# GECBalloonMCUFlightBoard_REV2_0_5-6-19.net
KiCad netlist of a schematic drawn in EAGLE
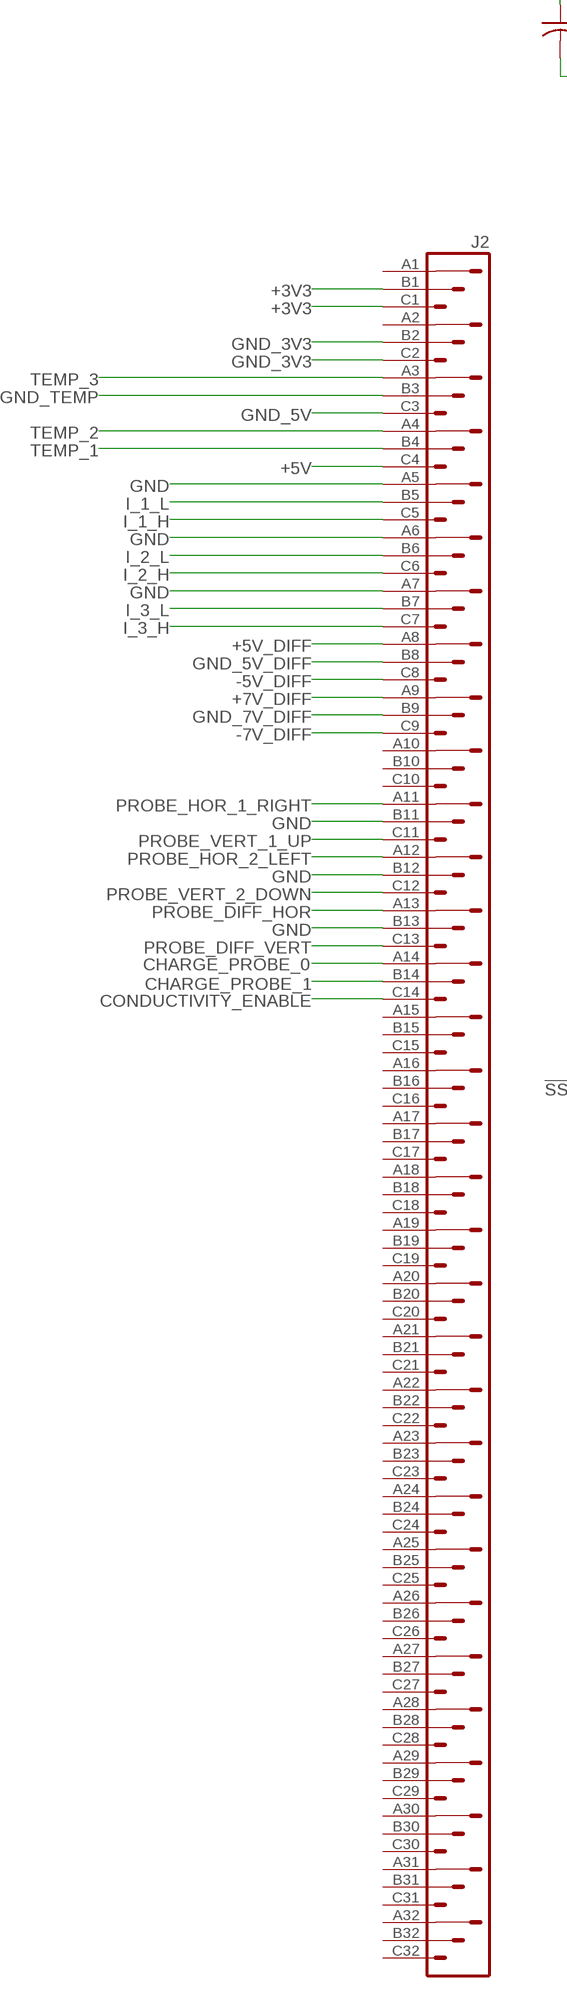
[diagram p0: schematic, sheet 1, part 1 of 2]
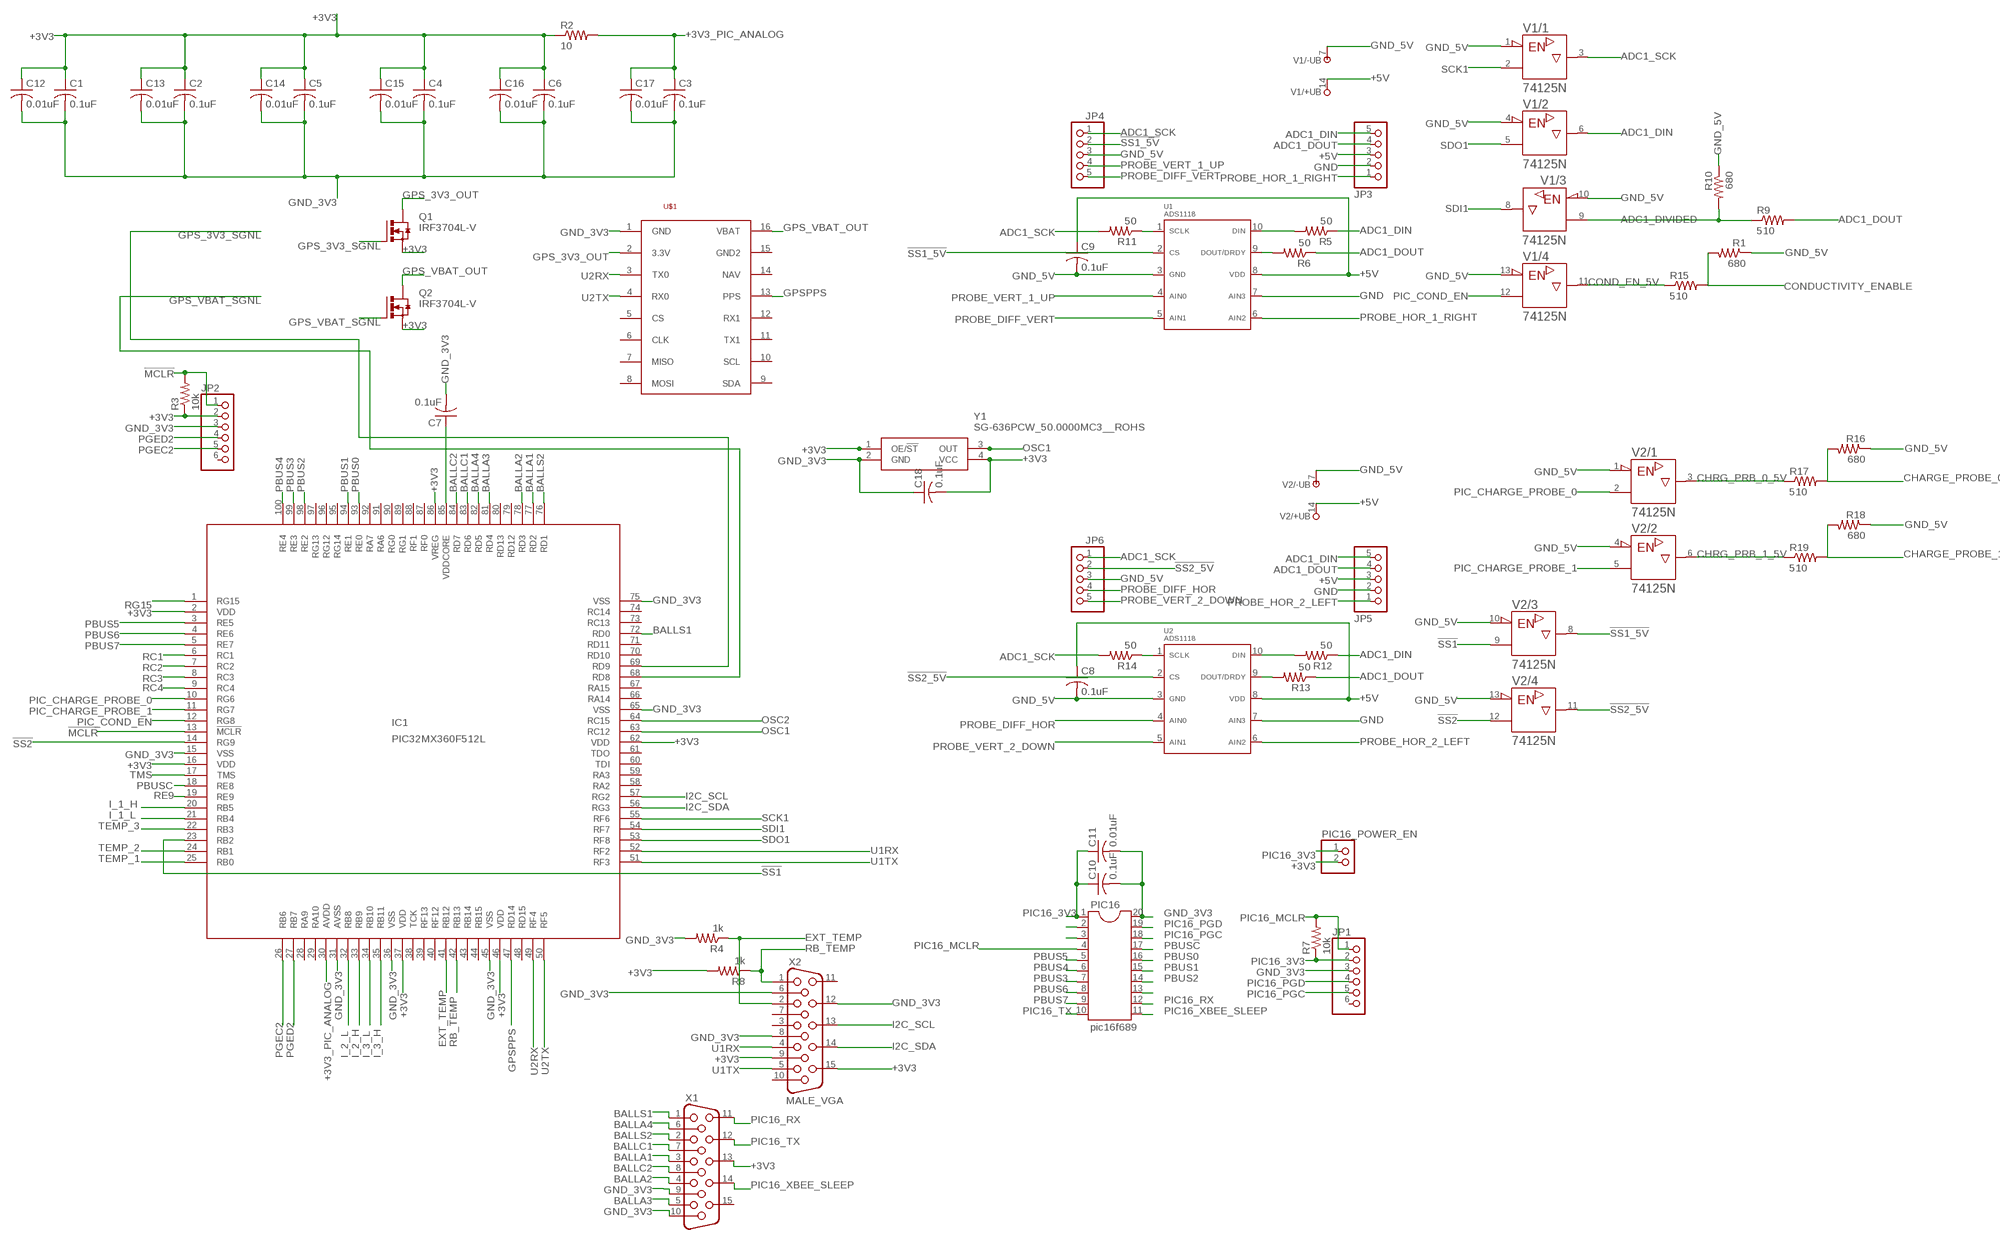
[diagram p1: schematic, sheet 1, part 2 of 2]

(export (version "E")
  (design (tool "Eeschema 10.0.6"))
  (components
    (comp (ref "C1")
      (value "0.1uF")
      (footprint "eagle-import:C1206")
      (libsource (lib "eagle-import") (part "C-USC1206"))
    )
    (comp (ref "C2")
      (value "0.1uF")
      (footprint "eagle-import:C1206")
      (libsource (lib "eagle-import") (part "C-USC1206"))
    )
    (comp (ref "C3")
      (value "0.1uF")
      (footprint "eagle-import:C1206")
      (libsource (lib "eagle-import") (part "C-USC1206"))
    )
    (comp (ref "C4")
      (value "0.1uF")
      (footprint "eagle-import:C1206")
      (libsource (lib "eagle-import") (part "C-USC1206"))
    )
    (comp (ref "C5")
      (value "0.1uF")
      (footprint "eagle-import:C1206")
      (libsource (lib "eagle-import") (part "C-USC1206"))
    )
    (comp (ref "C6")
      (value "0.1uF")
      (footprint "eagle-import:C1206")
      (libsource (lib "eagle-import") (part "C-USC1206"))
    )
    (comp (ref "C7")
      (value "0.1uF")
      (footprint "eagle-import:C1206")
      (libsource (lib "eagle-import") (part "C-USC1206"))
    )
    (comp (ref "C8")
      (value "0.1uF")
      (footprint "eagle-import:C1206")
      (libsource (lib "eagle-import") (part "C-USC1206"))
    )
    (comp (ref "C9")
      (value "0.1uF")
      (footprint "eagle-import:C1206")
      (libsource (lib "eagle-import") (part "C-USC1206"))
    )
    (comp (ref "C10")
      (value "0.1uF")
      (footprint "eagle-import:C1206")
      (libsource (lib "eagle-import") (part "C-USC1206"))
    )
    (comp (ref "C11")
      (value "0.01uF")
      (footprint "eagle-import:C1206")
      (libsource (lib "eagle-import") (part "C-USC1206"))
    )
    (comp (ref "C12")
      (value "0.01uF")
      (footprint "eagle-import:C1206")
      (libsource (lib "eagle-import") (part "C-USC1206"))
    )
    (comp (ref "C13")
      (value "0.01uF")
      (footprint "eagle-import:C1206")
      (libsource (lib "eagle-import") (part "C-USC1206"))
    )
    (comp (ref "C14")
      (value "0.01uF")
      (footprint "eagle-import:C1206")
      (libsource (lib "eagle-import") (part "C-USC1206"))
    )
    (comp (ref "C15")
      (value "0.01uF")
      (footprint "eagle-import:C1206")
      (libsource (lib "eagle-import") (part "C-USC1206"))
    )
    (comp (ref "C16")
      (value "0.01uF")
      (footprint "eagle-import:C1206")
      (libsource (lib "eagle-import") (part "C-USC1206"))
    )
    (comp (ref "C17")
      (value "0.01uF")
      (footprint "eagle-import:C1206")
      (libsource (lib "eagle-import") (part "C-USC1206"))
    )
    (comp (ref "C18")
      (value "0.1uF")
      (footprint "eagle-import:C1206")
      (libsource (lib "eagle-import") (part "C-USC1206"))
    )
    (comp (ref "IC1")
      (value "PIC32MX360F512L")
      (footprint "eagle-import:TQFP100")
      (libsource (lib "eagle-import") (part "PIC32MX360F512L"))
    )
    (comp (ref "J2")
      (value "VG96KB")
      (footprint "eagle-import:VG96KB")
      (libsource (lib "eagle-import") (part "VG96KB"))
    )
    (comp (ref "JP1")
      (value "PINHD-1X6")
      (footprint "eagle-import:1X06")
      (libsource (lib "eagle-import") (part "PINHD-1X6"))
    )
    (comp (ref "JP2")
      (value "PINHD-1X6")
      (footprint "eagle-import:1X06")
      (libsource (lib "eagle-import") (part "PINHD-1X6"))
    )
    (comp (ref "JP3")
      (value "PINHD-1X5")
      (footprint "eagle-import:1X05")
      (libsource (lib "eagle-import") (part "PINHD-1X5"))
    )
    (comp (ref "JP4")
      (value "PINHD-1X5")
      (footprint "eagle-import:1X05")
      (libsource (lib "eagle-import") (part "PINHD-1X5"))
    )
    (comp (ref "JP5")
      (value "PINHD-1X5")
      (footprint "eagle-import:1X05")
      (libsource (lib "eagle-import") (part "PINHD-1X5"))
    )
    (comp (ref "JP6")
      (value "PINHD-1X5")
      (footprint "eagle-import:1X05")
      (libsource (lib "eagle-import") (part "PINHD-1X5"))
    )
    (comp (ref "PIC16")
      (value "pic16f689")
      (footprint "eagle-import:DIL20")
      (libsource (lib "eagle-import") (part "DIL20"))
    )
    (comp (ref "PIC16_POWER_EN")
      (value "PINHD-1X2")
      (footprint "eagle-import:1X02")
      (libsource (lib "eagle-import") (part "PINHD-1X2"))
    )
    (comp (ref "Q1")
      (value "IRF3704L-V")
      (footprint "eagle-import:TO262-V")
      (libsource (lib "eagle-import") (part "IRF3704L-V"))
    )
    (comp (ref "Q2")
      (value "IRF3704L-V")
      (footprint "eagle-import:TO262-V")
      (libsource (lib "eagle-import") (part "IRF3704L-V"))
    )
    (comp (ref "R1")
      (value "680")
      (footprint "eagle-import:R1206")
      (libsource (lib "eagle-import") (part "resistor_R-US_R1206"))
    )
    (comp (ref "R2")
      (value "10")
      (footprint "eagle-import:M1206")
      (libsource (lib "eagle-import") (part "R-US_M1206"))
    )
    (comp (ref "R3")
      (value "10k")
      (footprint "eagle-import:M1206")
      (libsource (lib "eagle-import") (part "R-US_M1206"))
    )
    (comp (ref "R4")
      (value "1k")
      (footprint "eagle-import:0414_15")
      (libsource (lib "eagle-import") (part "resistor_R-US_0414/15"))
    )
    (comp (ref "R5")
      (value "50")
      (footprint "eagle-import:M1206")
      (libsource (lib "eagle-import") (part "R-US_M1206"))
    )
    (comp (ref "R6")
      (value "50")
      (footprint "eagle-import:M1206")
      (libsource (lib "eagle-import") (part "R-US_M1206"))
    )
    (comp (ref "R7")
      (value "10k")
      (footprint "eagle-import:M1206")
      (libsource (lib "eagle-import") (part "R-US_M1206"))
    )
    (comp (ref "R8")
      (value "1k")
      (footprint "eagle-import:0414_15")
      (libsource (lib "eagle-import") (part "resistor_R-US_0414/15"))
    )
    (comp (ref "R9")
      (value "510")
      (footprint "eagle-import:R1206")
      (libsource (lib "eagle-import") (part "resistor_R-US_R1206"))
    )
    (comp (ref "R10")
      (value "680")
      (footprint "eagle-import:R1206")
      (libsource (lib "eagle-import") (part "resistor_R-US_R1206"))
    )
    (comp (ref "R11")
      (value "50")
      (footprint "eagle-import:M1206")
      (libsource (lib "eagle-import") (part "R-US_M1206"))
    )
    (comp (ref "R12")
      (value "50")
      (footprint "eagle-import:M1206")
      (libsource (lib "eagle-import") (part "R-US_M1206"))
    )
    (comp (ref "R13")
      (value "50")
      (footprint "eagle-import:M1206")
      (libsource (lib "eagle-import") (part "R-US_M1206"))
    )
    (comp (ref "R14")
      (value "50")
      (footprint "eagle-import:M1206")
      (libsource (lib "eagle-import") (part "R-US_M1206"))
    )
    (comp (ref "R15")
      (value "510")
      (footprint "eagle-import:R1206")
      (libsource (lib "eagle-import") (part "resistor_R-US_R1206"))
    )
    (comp (ref "R16")
      (value "680")
      (footprint "eagle-import:R1206")
      (libsource (lib "eagle-import") (part "resistor_R-US_R1206"))
    )
    (comp (ref "R17")
      (value "510")
      (footprint "eagle-import:R1206")
      (libsource (lib "eagle-import") (part "resistor_R-US_R1206"))
    )
    (comp (ref "R18")
      (value "680")
      (footprint "eagle-import:R1206")
      (libsource (lib "eagle-import") (part "resistor_R-US_R1206"))
    )
    (comp (ref "R19")
      (value "510")
      (footprint "eagle-import:R1206")
      (libsource (lib "eagle-import") (part "resistor_R-US_R1206"))
    )
    (comp (ref "U$1")
      (value "SPARKFUN_VENUS_GPS_BREAKOUT")
      (footprint "eagle-import:SPARKFUN_BOARD")
      (libsource (lib "eagle-import") (part "SPARKFUN_VENUS_GPS_BREAKOUT"))
    )
    (comp (ref "U1")
      (value "ADS1118")
      (footprint "eagle-import:MSOP10")
      (libsource (lib "eagle-import") (part "ADS1118_MSOP10"))
    )
    (comp (ref "U2")
      (value "ADS1118")
      (footprint "eagle-import:MSOP10")
      (libsource (lib "eagle-import") (part "ADS1118_MSOP10"))
    )
    (comp (ref "V1")
      (value "74125N")
      (footprint "eagle-import:DIL14")
      (libsource (lib "eagle-import") (part "74125N"))
    )
    (comp (ref "V2")
      (value "74125N")
      (footprint "eagle-import:DIL14")
      (libsource (lib "eagle-import") (part "74125N"))
    )
    (comp (ref "X1")
      (value "HF15H")
      (footprint "eagle-import:HDF15H")
      (libsource (lib "eagle-import") (part "HF15H"))
    )
    (comp (ref "X2")
      (value "MALE_VGA")
      (footprint "eagle-import:MALE_PACKAGE")
      (libsource (lib "eagle-import") (part "MALE_VGA"))
    )
    (comp (ref "Y1")
      (value "SG-636PCW_50.0000MC3__ROHS")
      (footprint "eagle-import:SG-636")
      (fields (field (name "ARROW_PART_NUMBER") "SG-636PCW 50.0000MC3: ROHS"))
      (libsource (lib "eagle-import") (part "SG-636PCW_50.0000MC3__ROHS"))
    )
  )
  (nets
    (net (code "1") (name "/+3V3") (class "Default")
      (node (ref "C1") (pin "1") (pinfunction "1_1") (pintype "passive"))
      (node (ref "C12") (pin "1") (pinfunction "1_1") (pintype "passive"))
      (node (ref "C13") (pin "1") (pinfunction "1_1") (pintype "passive"))
      (node (ref "C14") (pin "1") (pinfunction "1_1") (pintype "passive"))
      (node (ref "C15") (pin "1") (pinfunction "1_1") (pintype "passive"))
      (node (ref "C16") (pin "1") (pinfunction "1_1") (pintype "passive"))
      (node (ref "C18") (pin "2") (pinfunction "2_2") (pintype "passive"))
      (node (ref "C2") (pin "1") (pinfunction "1_1") (pintype "passive"))
      (node (ref "C4") (pin "1") (pinfunction "1_1") (pintype "passive"))
      (node (ref "C5") (pin "1") (pinfunction "1_1") (pintype "passive"))
      (node (ref "C6") (pin "1") (pinfunction "1_1") (pintype "passive"))
      (node (ref "IC1") (pin "16") (pinfunction "VDD_16") (pintype "power_in"))
      (node (ref "IC1") (pin "2") (pinfunction "VDD_2") (pintype "power_in"))
      (node (ref "IC1") (pin "37") (pinfunction "VDD_37") (pintype "power_in"))
      (node (ref "IC1") (pin "46") (pinfunction "VDD_46") (pintype "power_in"))
      (node (ref "IC1") (pin "62") (pinfunction "VDD_62") (pintype "power_in"))
      (node (ref "IC1") (pin "86") (pinfunction "VREG_86") (pintype "passive"))
      (node (ref "J2") (pin "B1") (pinfunction "B1_B1") (pintype "passive"))
      (node (ref "J2") (pin "C1") (pinfunction "C1_C1") (pintype "passive"))
      (node (ref "JP2") (pin "2") (pinfunction "2_2") (pintype "passive"))
      (node (ref "PIC16_POWER_EN") (pin "2") (pinfunction "2_2") (pintype "passive"))
      (node (ref "Q1") (pin "3") (pinfunction "S_3") (pintype "passive"))
      (node (ref "Q2") (pin "3") (pinfunction "S_3") (pintype "passive"))
      (node (ref "R2") (pin "1") (pinfunction "1_1") (pintype "passive"))
      (node (ref "R3") (pin "1") (pinfunction "1_1") (pintype "passive"))
      (node (ref "R8") (pin "2") (pinfunction "2_2") (pintype "passive"))
      (node (ref "X1") (pin "13") (pinfunction "13_13") (pintype "passive"))
      (node (ref "X2") (pin "15") (pinfunction "15_15") (pintype "passive"))
      (node (ref "X2") (pin "9") (pinfunction "9_9") (pintype "passive"))
      (node (ref "Y1") (pin "1") (pinfunction "OE/~{ST}_1") (pintype "input"))
      (node (ref "Y1") (pin "4") (pinfunction "VCC_4") (pintype "power_in"))
    )
    (net (code "2") (name "/+3V3_PIC_ANALOG") (class "Default")
      (node (ref "C17") (pin "1") (pinfunction "1_1") (pintype "passive"))
      (node (ref "C3") (pin "1") (pinfunction "1_1") (pintype "passive"))
      (node (ref "IC1") (pin "30") (pinfunction "AVDD_30") (pintype "power_in"))
      (node (ref "R2") (pin "2") (pinfunction "2_2") (pintype "passive"))
    )
    (net (code "3") (name "/+5V") (class "Default")
      (node (ref "C8") (pin "1") (pinfunction "1_1") (pintype "passive"))
      (node (ref "C9") (pin "1") (pinfunction "1_1") (pintype "passive"))
      (node (ref "J2") (pin "C4") (pinfunction "C4_C4") (pintype "passive"))
      (node (ref "JP3") (pin "3") (pinfunction "3_3") (pintype "passive"))
      (node (ref "JP5") (pin "3") (pinfunction "3_3") (pintype "passive"))
      (node (ref "U1") (pin "8") (pinfunction "VDD_8") (pintype "bidirectional"))
      (node (ref "U2") (pin "8") (pinfunction "VDD_8") (pintype "bidirectional"))
      (node (ref "V1") (pin "14") (pinfunction "+UB_14") (pintype "power_in"))
      (node (ref "V2") (pin "14") (pinfunction "+UB_14") (pintype "power_in"))
    )
    (net (code "4") (name "/+5V_DIFF") (class "Default")
      (node (ref "J2") (pin "A8") (pinfunction "A8_A8") (pintype "passive"))
    )
    (net (code "5") (name "/+7V_DIFF") (class "Default")
      (node (ref "J2") (pin "A9") (pinfunction "A9_A9") (pintype "passive"))
    )
    (net (code "6") (name "/-5V_DIFF") (class "Default")
      (node (ref "J2") (pin "C8") (pinfunction "C8_C8") (pintype "passive"))
    )
    (net (code "7") (name "/-7V_DIFF") (class "Default")
      (node (ref "J2") (pin "C9") (pinfunction "C9_C9") (pintype "passive"))
    )
    (net (code "8") (name "/ADC1_DIN") (class "Default")
      (node (ref "JP3") (pin "5") (pinfunction "5_5") (pintype "passive"))
      (node (ref "JP5") (pin "5") (pinfunction "5_5") (pintype "passive"))
      (node (ref "R12") (pin "1") (pinfunction "1_1") (pintype "passive"))
      (node (ref "R5") (pin "1") (pinfunction "1_1") (pintype "passive"))
      (node (ref "V1") (pin "6") (pinfunction "Y_6") (pintype "tri_state"))
    )
    (net (code "9") (name "/ADC1_DIVIDED") (class "Default")
      (node (ref "R10") (pin "2") (pinfunction "2_2") (pintype "passive"))
      (node (ref "R9") (pin "1") (pinfunction "1_1") (pintype "passive"))
      (node (ref "V1") (pin "9") (pinfunction "A_9") (pintype "input"))
    )
    (net (code "10") (name "/ADC1_DOUT") (class "Default")
      (node (ref "JP3") (pin "4") (pinfunction "4_4") (pintype "passive"))
      (node (ref "JP5") (pin "4") (pinfunction "4_4") (pintype "passive"))
      (node (ref "R13") (pin "1") (pinfunction "1_1") (pintype "passive"))
      (node (ref "R6") (pin "1") (pinfunction "1_1") (pintype "passive"))
      (node (ref "R9") (pin "2") (pinfunction "2_2") (pintype "passive"))
    )
    (net (code "11") (name "/ADC1_SCK") (class "Default")
      (node (ref "JP4") (pin "1") (pinfunction "1_1") (pintype "passive"))
      (node (ref "JP6") (pin "1") (pinfunction "1_1") (pintype "passive"))
      (node (ref "R11") (pin "2") (pinfunction "2_2") (pintype "passive"))
      (node (ref "R14") (pin "2") (pinfunction "2_2") (pintype "passive"))
      (node (ref "V1") (pin "3") (pinfunction "Y_3") (pintype "tri_state"))
    )
    (net (code "12") (name "/BALLA1") (class "Default")
      (node (ref "IC1") (pin "77") (pinfunction "RD2_77") (pintype "bidirectional"))
      (node (ref "X1") (pin "3") (pinfunction "3_3") (pintype "passive"))
    )
    (net (code "13") (name "/BALLA2") (class "Default")
      (node (ref "IC1") (pin "78") (pinfunction "RD3_78") (pintype "bidirectional"))
      (node (ref "X1") (pin "4") (pinfunction "4_4") (pintype "passive"))
    )
    (net (code "14") (name "/BALLA3") (class "Default")
      (node (ref "IC1") (pin "81") (pinfunction "RD4_81") (pintype "bidirectional"))
      (node (ref "X1") (pin "5") (pinfunction "5_5") (pintype "passive"))
    )
    (net (code "15") (name "/BALLA4") (class "Default")
      (node (ref "IC1") (pin "82") (pinfunction "RD5_82") (pintype "bidirectional"))
      (node (ref "X1") (pin "6") (pinfunction "6_6") (pintype "passive"))
    )
    (net (code "16") (name "/BALLC1") (class "Default")
      (node (ref "IC1") (pin "83") (pinfunction "RD6_83") (pintype "bidirectional"))
      (node (ref "X1") (pin "7") (pinfunction "7_7") (pintype "passive"))
    )
    (net (code "17") (name "/BALLC2") (class "Default")
      (node (ref "IC1") (pin "84") (pinfunction "RD7_84") (pintype "bidirectional"))
      (node (ref "X1") (pin "8") (pinfunction "8_8") (pintype "passive"))
    )
    (net (code "18") (name "/BALLS1") (class "Default")
      (node (ref "IC1") (pin "72") (pinfunction "RD0_72") (pintype "bidirectional"))
      (node (ref "X1") (pin "1") (pinfunction "1_1") (pintype "passive"))
    )
    (net (code "19") (name "/BALLS2") (class "Default")
      (node (ref "IC1") (pin "76") (pinfunction "RD1_76") (pintype "bidirectional"))
      (node (ref "X1") (pin "2") (pinfunction "2_2") (pintype "passive"))
    )
    (net (code "20") (name "/CHARGE_PROBE_0") (class "Default")
      (node (ref "J2") (pin "A14") (pinfunction "A14_A14") (pintype "passive"))
      (node (ref "R16") (pin "2") (pinfunction "2_2") (pintype "passive"))
      (node (ref "R17") (pin "2") (pinfunction "2_2") (pintype "passive"))
    )
    (net (code "21") (name "/CHARGE_PROBE_1") (class "Default")
      (node (ref "J2") (pin "B14") (pinfunction "B14_B14") (pintype "passive"))
      (node (ref "R18") (pin "2") (pinfunction "2_2") (pintype "passive"))
      (node (ref "R19") (pin "2") (pinfunction "2_2") (pintype "passive"))
    )
    (net (code "22") (name "/CHRG_PRB_0_5V") (class "Default")
      (node (ref "R17") (pin "1") (pinfunction "1_1") (pintype "passive"))
      (node (ref "V2") (pin "3") (pinfunction "Y_3") (pintype "tri_state"))
    )
    (net (code "23") (name "/CHRG_PRB_1_5V") (class "Default")
      (node (ref "R19") (pin "1") (pinfunction "1_1") (pintype "passive"))
      (node (ref "V2") (pin "6") (pinfunction "Y_6") (pintype "tri_state"))
    )
    (net (code "24") (name "/CONDUCTIVITY_ENABLE") (class "Default")
      (node (ref "J2") (pin "C14") (pinfunction "C14_C14") (pintype "passive"))
      (node (ref "R1") (pin "2") (pinfunction "2_2") (pintype "passive"))
      (node (ref "R15") (pin "2") (pinfunction "2_2") (pintype "passive"))
    )
    (net (code "25") (name "/COND_EN_5V") (class "Default")
      (node (ref "R15") (pin "1") (pinfunction "1_1") (pintype "passive"))
      (node (ref "V1") (pin "11") (pinfunction "Y_11") (pintype "tri_state"))
    )
    (net (code "26") (name "/EXT_TEMP") (class "Default")
      (node (ref "IC1") (pin "41") (pinfunction "RB12_41") (pintype "bidirectional"))
      (node (ref "R4") (pin "1") (pinfunction "1_1") (pintype "passive"))
      (node (ref "X2") (pin "2") (pinfunction "2_2") (pintype "passive"))
    )
    (net (code "27") (name "/GND") (class "Default")
      (node (ref "J2") (pin "A5") (pinfunction "A5_A5") (pintype "passive"))
      (node (ref "J2") (pin "A6") (pinfunction "A6_A6") (pintype "passive"))
      (node (ref "J2") (pin "A7") (pinfunction "A7_A7") (pintype "passive"))
      (node (ref "J2") (pin "B11") (pinfunction "B11_B11") (pintype "passive"))
      (node (ref "J2") (pin "B12") (pinfunction "B12_B12") (pintype "passive"))
      (node (ref "J2") (pin "B13") (pinfunction "B13_B13") (pintype "passive"))
      (node (ref "JP3") (pin "2") (pinfunction "2_2") (pintype "passive"))
      (node (ref "JP5") (pin "2") (pinfunction "2_2") (pintype "passive"))
      (node (ref "U1") (pin "7") (pinfunction "AIN3_7") (pintype "bidirectional"))
      (node (ref "U2") (pin "7") (pinfunction "AIN3_7") (pintype "bidirectional"))
    )
    (net (code "28") (name "/GND_3V3") (class "Default")
      (node (ref "C1") (pin "2") (pinfunction "2_2") (pintype "passive"))
      (node (ref "C10") (pin "2") (pinfunction "2_2") (pintype "passive"))
      (node (ref "C11") (pin "2") (pinfunction "2_2") (pintype "passive"))
      (node (ref "C12") (pin "2") (pinfunction "2_2") (pintype "passive"))
      (node (ref "C13") (pin "2") (pinfunction "2_2") (pintype "passive"))
      (node (ref "C14") (pin "2") (pinfunction "2_2") (pintype "passive"))
      (node (ref "C15") (pin "2") (pinfunction "2_2") (pintype "passive"))
      (node (ref "C16") (pin "2") (pinfunction "2_2") (pintype "passive"))
      (node (ref "C17") (pin "2") (pinfunction "2_2") (pintype "passive"))
      (node (ref "C18") (pin "1") (pinfunction "1_1") (pintype "passive"))
      (node (ref "C2") (pin "2") (pinfunction "2_2") (pintype "passive"))
      (node (ref "C3") (pin "2") (pinfunction "2_2") (pintype "passive"))
      (node (ref "C4") (pin "2") (pinfunction "2_2") (pintype "passive"))
      (node (ref "C5") (pin "2") (pinfunction "2_2") (pintype "passive"))
      (node (ref "C6") (pin "2") (pinfunction "2_2") (pintype "passive"))
      (node (ref "C7") (pin "2") (pinfunction "2_2") (pintype "passive"))
      (node (ref "IC1") (pin "15") (pinfunction "VSS_15") (pintype "power_in"))
      (node (ref "IC1") (pin "31") (pinfunction "AVSS_31") (pintype "power_in"))
      (node (ref "IC1") (pin "36") (pinfunction "VSS_36") (pintype "power_in"))
      (node (ref "IC1") (pin "45") (pinfunction "VSS_45") (pintype "power_in"))
      (node (ref "IC1") (pin "65") (pinfunction "VSS_65") (pintype "power_in"))
      (node (ref "IC1") (pin "75") (pinfunction "VSS_75") (pintype "power_in"))
      (node (ref "J2") (pin "B2") (pinfunction "B2_B2") (pintype "passive"))
      (node (ref "J2") (pin "C2") (pinfunction "C2_C2") (pintype "passive"))
      (node (ref "JP1") (pin "3") (pinfunction "3_3") (pintype "passive"))
      (node (ref "JP2") (pin "3") (pinfunction "3_3") (pintype "passive"))
      (node (ref "PIC16") (pin "20") (pinfunction "20_20") (pintype "passive"))
      (node (ref "R4") (pin "2") (pinfunction "2_2") (pintype "passive"))
      (node (ref "U$1") (pin "1") (pinfunction "GND_1") (pintype "bidirectional"))
      (node (ref "X1") (pin "10") (pinfunction "10_10") (pintype "passive"))
      (node (ref "X1") (pin "9") (pinfunction "9_9") (pintype "passive"))
      (node (ref "X2") (pin "12") (pinfunction "12_12") (pintype "passive"))
      (node (ref "X2") (pin "6") (pinfunction "6_6") (pintype "passive"))
      (node (ref "X2") (pin "8") (pinfunction "8_8") (pintype "passive"))
      (node (ref "Y1") (pin "2") (pinfunction "GND_2") (pintype "power_in"))
    )
    (net (code "29") (name "/GND_5V") (class "Default")
      (node (ref "C8") (pin "2") (pinfunction "2_2") (pintype "passive"))
      (node (ref "C9") (pin "2") (pinfunction "2_2") (pintype "passive"))
      (node (ref "J2") (pin "C3") (pinfunction "C3_C3") (pintype "passive"))
      (node (ref "JP4") (pin "3") (pinfunction "3_3") (pintype "passive"))
      (node (ref "JP6") (pin "3") (pinfunction "3_3") (pintype "passive"))
      (node (ref "R1") (pin "1") (pinfunction "1_1") (pintype "passive"))
      (node (ref "R10") (pin "1") (pinfunction "1_1") (pintype "passive"))
      (node (ref "R16") (pin "1") (pinfunction "1_1") (pintype "passive"))
      (node (ref "R18") (pin "1") (pinfunction "1_1") (pintype "passive"))
      (node (ref "U1") (pin "3") (pinfunction "GND_3") (pintype "bidirectional"))
      (node (ref "U2") (pin "3") (pinfunction "GND_3") (pintype "bidirectional"))
      (node (ref "V1") (pin "1") (pinfunction "~{G}_1") (pintype "input"))
      (node (ref "V1") (pin "10") (pinfunction "~{G}_10") (pintype "input"))
      (node (ref "V1") (pin "13") (pinfunction "~{G}_13") (pintype "input"))
      (node (ref "V1") (pin "4") (pinfunction "~{G}_4") (pintype "input"))
      (node (ref "V1") (pin "7") (pinfunction "-UB_7") (pintype "power_in"))
      (node (ref "V2") (pin "1") (pinfunction "~{G}_1") (pintype "input"))
      (node (ref "V2") (pin "10") (pinfunction "~{G}_10") (pintype "input"))
      (node (ref "V2") (pin "13") (pinfunction "~{G}_13") (pintype "input"))
      (node (ref "V2") (pin "4") (pinfunction "~{G}_4") (pintype "input"))
      (node (ref "V2") (pin "7") (pinfunction "-UB_7") (pintype "power_in"))
    )
    (net (code "30") (name "/GND_5V_DIFF") (class "Default")
      (node (ref "J2") (pin "B8") (pinfunction "B8_B8") (pintype "passive"))
    )
    (net (code "31") (name "/GND_7V_DIFF") (class "Default")
      (node (ref "J2") (pin "B9") (pinfunction "B9_B9") (pintype "passive"))
    )
    (net (code "32") (name "/GND_TEMP") (class "Default")
      (node (ref "J2") (pin "B3") (pinfunction "B3_B3") (pintype "passive"))
    )
    (net (code "33") (name "/GPSPPS") (class "Default")
      (node (ref "IC1") (pin "47") (pinfunction "RD14_47") (pintype "bidirectional"))
      (node (ref "U$1") (pin "13") (pinfunction "PPS_13") (pintype "bidirectional"))
    )
    (net (code "34") (name "/GPS_3V3_OUT") (class "Default")
      (node (ref "Q1") (pin "2") (pinfunction "D_2") (pintype "passive"))
      (node (ref "U$1") (pin "2") (pinfunction "3.3V_2") (pintype "bidirectional"))
    )
    (net (code "35") (name "/GPS_3V3_SGNL") (class "Default")
      (node (ref "IC1") (pin "69") (pinfunction "RD9_69") (pintype "bidirectional"))
      (node (ref "Q1") (pin "1") (pinfunction "G_1") (pintype "passive"))
    )
    (net (code "36") (name "/GPS_VBAT_OUT") (class "Default")
      (node (ref "Q2") (pin "2") (pinfunction "D_2") (pintype "passive"))
      (node (ref "U$1") (pin "16") (pinfunction "VBAT_16") (pintype "bidirectional"))
    )
    (net (code "37") (name "/GPS_VBAT_SGNL") (class "Default")
      (node (ref "IC1") (pin "68") (pinfunction "RD8_68") (pintype "bidirectional"))
      (node (ref "Q2") (pin "1") (pinfunction "G_1") (pintype "passive"))
    )
    (net (code "38") (name "/I2C_SCL") (class "Default")
      (node (ref "IC1") (pin "57") (pinfunction "RG2_57") (pintype "bidirectional"))
      (node (ref "X2") (pin "13") (pinfunction "13_13") (pintype "passive"))
    )
    (net (code "39") (name "/I2C_SDA") (class "Default")
      (node (ref "IC1") (pin "56") (pinfunction "RG3_56") (pintype "bidirectional"))
      (node (ref "X2") (pin "14") (pinfunction "14_14") (pintype "passive"))
    )
    (net (code "40") (name "/I_1_H") (class "Default")
      (node (ref "IC1") (pin "20") (pinfunction "RB5_20") (pintype "bidirectional"))
      (node (ref "J2") (pin "C5") (pinfunction "C5_C5") (pintype "passive"))
    )
    (net (code "41") (name "/I_1_L") (class "Default")
      (node (ref "IC1") (pin "21") (pinfunction "RB4_21") (pintype "bidirectional"))
      (node (ref "J2") (pin "B5") (pinfunction "B5_B5") (pintype "passive"))
    )
    (net (code "42") (name "/I_2_H") (class "Default")
      (node (ref "IC1") (pin "33") (pinfunction "RB9_33") (pintype "bidirectional"))
      (node (ref "J2") (pin "C6") (pinfunction "C6_C6") (pintype "passive"))
    )
    (net (code "43") (name "/I_2_L") (class "Default")
      (node (ref "IC1") (pin "32") (pinfunction "RB8_32") (pintype "bidirectional"))
      (node (ref "J2") (pin "B6") (pinfunction "B6_B6") (pintype "passive"))
    )
    (net (code "44") (name "/I_3_H") (class "Default")
      (node (ref "IC1") (pin "35") (pinfunction "RB11_35") (pintype "bidirectional"))
      (node (ref "J2") (pin "C7") (pinfunction "C7_C7") (pintype "passive"))
    )
    (net (code "45") (name "/I_3_L") (class "Default")
      (node (ref "IC1") (pin "34") (pinfunction "RB10_34") (pintype "bidirectional"))
      (node (ref "J2") (pin "B7") (pinfunction "B7_B7") (pintype "passive"))
    )
    (net (code "46") (name "/OSC1") (class "Default")
      (node (ref "IC1") (pin "63") (pinfunction "RC12_63") (pintype "bidirectional"))
      (node (ref "Y1") (pin "3") (pinfunction "OUT_3") (pintype "output"))
    )
    (net (code "47") (name "/OSC2") (class "Default")
      (node (ref "IC1") (pin "64") (pinfunction "RC15_64") (pintype "bidirectional"))
    )
    (net (code "48") (name "/PBUS0") (class "Default")
      (node (ref "IC1") (pin "93") (pinfunction "RE0_93") (pintype "bidirectional"))
      (node (ref "PIC16") (pin "16") (pinfunction "16_16") (pintype "passive"))
    )
    (net (code "49") (name "/PBUS1") (class "Default")
      (node (ref "IC1") (pin "94") (pinfunction "RE1_94") (pintype "bidirectional"))
      (node (ref "PIC16") (pin "15") (pinfunction "15_15") (pintype "passive"))
    )
    (net (code "50") (name "/PBUS2") (class "Default")
      (node (ref "IC1") (pin "98") (pinfunction "RE2_98") (pintype "bidirectional"))
      (node (ref "PIC16") (pin "14") (pinfunction "14_14") (pintype "passive"))
    )
    (net (code "51") (name "/PBUS3") (class "Default")
      (node (ref "IC1") (pin "99") (pinfunction "RE3_99") (pintype "bidirectional"))
      (node (ref "PIC16") (pin "7") (pinfunction "7_7") (pintype "passive"))
    )
    (net (code "52") (name "/PBUS4") (class "Default")
      (node (ref "IC1") (pin "100") (pinfunction "RE4_100") (pintype "bidirectional"))
      (node (ref "PIC16") (pin "6") (pinfunction "6_6") (pintype "passive"))
    )
    (net (code "53") (name "/PBUS5") (class "Default")
      (node (ref "IC1") (pin "3") (pinfunction "RE5_3") (pintype "bidirectional"))
      (node (ref "PIC16") (pin "5") (pinfunction "5_5") (pintype "passive"))
    )
    (net (code "54") (name "/PBUS6") (class "Default")
      (node (ref "IC1") (pin "4") (pinfunction "RE6_4") (pintype "bidirectional"))
      (node (ref "PIC16") (pin "8") (pinfunction "8_8") (pintype "passive"))
    )
    (net (code "55") (name "/PBUS7") (class "Default")
      (node (ref "IC1") (pin "5") (pinfunction "RE7_5") (pintype "bidirectional"))
      (node (ref "PIC16") (pin "9") (pinfunction "9_9") (pintype "passive"))
    )
    (net (code "56") (name "/PBUSC") (class "Default")
      (node (ref "IC1") (pin "18") (pinfunction "RE8_18") (pintype "bidirectional"))
      (node (ref "PIC16") (pin "17") (pinfunction "17_17") (pintype "passive"))
    )
    (net (code "57") (name "/PGEC2") (class "Default")
      (node (ref "IC1") (pin "26") (pinfunction "RB6_26") (pintype "bidirectional"))
      (node (ref "JP2") (pin "5") (pinfunction "5_5") (pintype "passive"))
    )
    (net (code "58") (name "/PGED2") (class "Default")
      (node (ref "IC1") (pin "27") (pinfunction "RB7_27") (pintype "bidirectional"))
      (node (ref "JP2") (pin "4") (pinfunction "4_4") (pintype "passive"))
    )
    (net (code "59") (name "/PIC16_3V3") (class "Default")
      (node (ref "C10") (pin "1") (pinfunction "1_1") (pintype "passive"))
      (node (ref "C11") (pin "1") (pinfunction "1_1") (pintype "passive"))
      (node (ref "JP1") (pin "2") (pinfunction "2_2") (pintype "passive"))
      (node (ref "PIC16") (pin "1") (pinfunction "1_1") (pintype "passive"))
      (node (ref "PIC16_POWER_EN") (pin "1") (pinfunction "1_1") (pintype "passive"))
      (node (ref "R7") (pin "1") (pinfunction "1_1") (pintype "passive"))
    )
    (net (code "60") (name "/PIC16_MCLR") (class "Default")
      (node (ref "JP1") (pin "1") (pinfunction "1_1") (pintype "passive"))
      (node (ref "PIC16") (pin "4") (pinfunction "4_4") (pintype "passive"))
      (node (ref "R7") (pin "2") (pinfunction "2_2") (pintype "passive"))
    )
    (net (code "61") (name "/PIC16_PGC") (class "Default")
      (node (ref "JP1") (pin "5") (pinfunction "5_5") (pintype "passive"))
      (node (ref "PIC16") (pin "18") (pinfunction "18_18") (pintype "passive"))
    )
    (net (code "62") (name "/PIC16_PGD") (class "Default")
      (node (ref "JP1") (pin "4") (pinfunction "4_4") (pintype "passive"))
      (node (ref "PIC16") (pin "19") (pinfunction "19_19") (pintype "passive"))
    )
    (net (code "63") (name "/PIC16_RX") (class "Default")
      (node (ref "PIC16") (pin "12") (pinfunction "12_12") (pintype "passive"))
      (node (ref "X1") (pin "11") (pinfunction "11_11") (pintype "passive"))
    )
    (net (code "64") (name "/PIC16_TX") (class "Default")
      (node (ref "PIC16") (pin "10") (pinfunction "10_10") (pintype "passive"))
      (node (ref "X1") (pin "12") (pinfunction "12_12") (pintype "passive"))
    )
    (net (code "65") (name "/PIC16_XBEE_SLEEP") (class "Default")
      (node (ref "PIC16") (pin "11") (pinfunction "11_11") (pintype "passive"))
      (node (ref "X1") (pin "14") (pinfunction "14_14") (pintype "passive"))
    )
    (net (code "66") (name "/PIC_CHARGE_PROBE_0") (class "Default")
      (node (ref "IC1") (pin "10") (pinfunction "RG6_10") (pintype "bidirectional"))
      (node (ref "V2") (pin "2") (pinfunction "A_2") (pintype "input"))
    )
    (net (code "67") (name "/PIC_CHARGE_PROBE_1") (class "Default")
      (node (ref "IC1") (pin "11") (pinfunction "RG7_11") (pintype "bidirectional"))
      (node (ref "V2") (pin "5") (pinfunction "A_5") (pintype "input"))
    )
    (net (code "68") (name "/PIC_COND_EN") (class "Default")
      (node (ref "IC1") (pin "12") (pinfunction "RG8_12") (pintype "bidirectional"))
      (node (ref "V1") (pin "12") (pinfunction "A_12") (pintype "input"))
    )
    (net (code "69") (name "/PROBE_DIFF_HOR") (class "Default")
      (node (ref "J2") (pin "A13") (pinfunction "A13_A13") (pintype "passive"))
      (node (ref "JP6") (pin "4") (pinfunction "4_4") (pintype "passive"))
      (node (ref "U2") (pin "4") (pinfunction "AIN0_4") (pintype "bidirectional"))
    )
    (net (code "70") (name "/PROBE_DIFF_VERT") (class "Default")
      (node (ref "J2") (pin "C13") (pinfunction "C13_C13") (pintype "passive"))
      (node (ref "JP4") (pin "5") (pinfunction "5_5") (pintype "passive"))
      (node (ref "U1") (pin "5") (pinfunction "AIN1_5") (pintype "bidirectional"))
    )
    (net (code "71") (name "/PROBE_HOR_1_RIGHT") (class "Default")
      (node (ref "J2") (pin "A11") (pinfunction "A11_A11") (pintype "passive"))
      (node (ref "JP3") (pin "1") (pinfunction "1_1") (pintype "passive"))
      (node (ref "U1") (pin "6") (pinfunction "AIN2_6") (pintype "bidirectional"))
    )
    (net (code "72") (name "/PROBE_HOR_2_LEFT") (class "Default")
      (node (ref "J2") (pin "A12") (pinfunction "A12_A12") (pintype "passive"))
      (node (ref "JP5") (pin "1") (pinfunction "1_1") (pintype "passive"))
      (node (ref "U2") (pin "6") (pinfunction "AIN2_6") (pintype "bidirectional"))
    )
    (net (code "73") (name "/PROBE_VERT_1_UP") (class "Default")
      (node (ref "J2") (pin "C11") (pinfunction "C11_C11") (pintype "passive"))
      (node (ref "JP4") (pin "4") (pinfunction "4_4") (pintype "passive"))
      (node (ref "U1") (pin "4") (pinfunction "AIN0_4") (pintype "bidirectional"))
    )
    (net (code "74") (name "/PROBE_VERT_2_DOWN") (class "Default")
      (node (ref "J2") (pin "C12") (pinfunction "C12_C12") (pintype "passive"))
      (node (ref "JP6") (pin "5") (pinfunction "5_5") (pintype "passive"))
      (node (ref "U2") (pin "5") (pinfunction "AIN1_5") (pintype "bidirectional"))
    )
    (net (code "75") (name "/RB_TEMP") (class "Default")
      (node (ref "IC1") (pin "42") (pinfunction "RB13_42") (pintype "bidirectional"))
      (node (ref "R8") (pin "1") (pinfunction "1_1") (pintype "passive"))
      (node (ref "X2") (pin "1") (pinfunction "1_1") (pintype "passive"))
    )
    (net (code "76") (name "/RC1") (class "Default")
      (node (ref "IC1") (pin "6") (pinfunction "RC1_6") (pintype "bidirectional"))
    )
    (net (code "77") (name "/RC2") (class "Default")
      (node (ref "IC1") (pin "7") (pinfunction "RC2_7") (pintype "bidirectional"))
    )
    (net (code "78") (name "/RC3") (class "Default")
      (node (ref "IC1") (pin "8") (pinfunction "RC3_8") (pintype "bidirectional"))
    )
    (net (code "79") (name "/RC4") (class "Default")
      (node (ref "IC1") (pin "9") (pinfunction "RC4_9") (pintype "bidirectional"))
    )
    (net (code "80") (name "/RE9") (class "Default")
      (node (ref "IC1") (pin "19") (pinfunction "RE9_19") (pintype "bidirectional"))
    )
    (net (code "81") (name "/RG15") (class "Default")
      (node (ref "IC1") (pin "1") (pinfunction "RG15_1") (pintype "bidirectional"))
    )
    (net (code "82") (name "/SCK1") (class "Default")
      (node (ref "IC1") (pin "55") (pinfunction "RF6_55") (pintype "bidirectional"))
      (node (ref "V1") (pin "2") (pinfunction "A_2") (pintype "input"))
    )
    (net (code "83") (name "/SDI1") (class "Default")
      (node (ref "IC1") (pin "54") (pinfunction "RF7_54") (pintype "bidirectional"))
      (node (ref "V1") (pin "8") (pinfunction "Y_8") (pintype "tri_state"))
    )
    (net (code "84") (name "/SDO1") (class "Default")
      (node (ref "IC1") (pin "53") (pinfunction "RF8_53") (pintype "bidirectional"))
      (node (ref "V1") (pin "5") (pinfunction "A_5") (pintype "input"))
    )
    (net (code "85") (name "/TEMP_1") (class "Default")
      (node (ref "IC1") (pin "25") (pinfunction "RB0_25") (pintype "bidirectional"))
      (node (ref "J2") (pin "B4") (pinfunction "B4_B4") (pintype "passive"))
    )
    (net (code "86") (name "/TEMP_2") (class "Default")
      (node (ref "IC1") (pin "24") (pinfunction "RB1_24") (pintype "bidirectional"))
      (node (ref "J2") (pin "A4") (pinfunction "A4_A4") (pintype "passive"))
    )
    (net (code "87") (name "/TEMP_3") (class "Default")
      (node (ref "IC1") (pin "22") (pinfunction "RB3_22") (pintype "bidirectional"))
      (node (ref "J2") (pin "A3") (pinfunction "A3_A3") (pintype "passive"))
    )
    (net (code "88") (name "/TMS") (class "Default")
      (node (ref "IC1") (pin "17") (pinfunction "TMS_17") (pintype "input"))
    )
    (net (code "89") (name "/U1RX") (class "Default")
      (node (ref "IC1") (pin "52") (pinfunction "RF2_52") (pintype "bidirectional"))
      (node (ref "X2") (pin "4") (pinfunction "4_4") (pintype "passive"))
    )
    (net (code "90") (name "/U1TX") (class "Default")
      (node (ref "IC1") (pin "51") (pinfunction "RF3_51") (pintype "bidirectional"))
      (node (ref "X2") (pin "5") (pinfunction "5_5") (pintype "passive"))
    )
    (net (code "91") (name "/U2RX") (class "Default")
      (node (ref "IC1") (pin "49") (pinfunction "RF4_49") (pintype "bidirectional"))
      (node (ref "U$1") (pin "3") (pinfunction "TX0_3") (pintype "bidirectional"))
    )
    (net (code "92") (name "/U2TX") (class "Default")
      (node (ref "IC1") (pin "50") (pinfunction "RF5_50") (pintype "bidirectional"))
      (node (ref "U$1") (pin "4") (pinfunction "RX0_4") (pintype "bidirectional"))
    )
    (net (code "93") (name "/~{MCLR}") (class "Default")
      (node (ref "IC1") (pin "13") (pinfunction "~{MCLR}_13") (pintype "input"))
      (node (ref "JP2") (pin "1") (pinfunction "1_1") (pintype "passive"))
      (node (ref "R3") (pin "2") (pinfunction "2_2") (pintype "passive"))
    )
    (net (code "94") (name "/~{SS1_5V}") (class "Default")
      (node (ref "JP4") (pin "2") (pinfunction "2_2") (pintype "passive"))
      (node (ref "U1") (pin "2") (pinfunction "CS_2") (pintype "bidirectional"))
      (node (ref "V2") (pin "8") (pinfunction "Y_8") (pintype "tri_state"))
    )
    (net (code "95") (name "/~{SS1}") (class "Default")
      (node (ref "IC1") (pin "23") (pinfunction "RB2_23") (pintype "bidirectional"))
      (node (ref "V2") (pin "9") (pinfunction "A_9") (pintype "input"))
    )
    (net (code "96") (name "/~{SS2_5V}") (class "Default")
      (node (ref "JP6") (pin "2") (pinfunction "2_2") (pintype "passive"))
      (node (ref "U2") (pin "2") (pinfunction "CS_2") (pintype "bidirectional"))
      (node (ref "V2") (pin "11") (pinfunction "Y_11") (pintype "tri_state"))
    )
    (net (code "97") (name "/~{SS2}") (class "Default")
      (node (ref "IC1") (pin "14") (pinfunction "RG9_14") (pintype "bidirectional"))
      (node (ref "V2") (pin "12") (pinfunction "A_12") (pintype "input"))
    )
    (net (code "98") (name "Net-(IC1-VDDCORE)") (class "Default")
      (node (ref "C7") (pin "1") (pinfunction "1_1") (pintype "passive"))
      (node (ref "IC1") (pin "85") (pinfunction "VDDCORE_85") (pintype "power_in"))
    )
    (net (code "99") (name "Net-(U1-DIN)") (class "Default")
      (node (ref "R5") (pin "2") (pinfunction "2_2") (pintype "passive"))
      (node (ref "U1") (pin "10") (pinfunction "DIN_10") (pintype "bidirectional"))
    )
    (net (code "100") (name "Net-(U1-DOUT{slash}DRDY)") (class "Default")
      (node (ref "R6") (pin "2") (pinfunction "2_2") (pintype "passive"))
      (node (ref "U1") (pin "9") (pinfunction "DOUT/DRDY_9") (pintype "bidirectional"))
    )
    (net (code "101") (name "Net-(U1-SCLK)") (class "Default")
      (node (ref "R11") (pin "1") (pinfunction "1_1") (pintype "passive"))
      (node (ref "U1") (pin "1") (pinfunction "SCLK_1") (pintype "bidirectional"))
    )
    (net (code "102") (name "Net-(U2-DIN)") (class "Default")
      (node (ref "R12") (pin "2") (pinfunction "2_2") (pintype "passive"))
      (node (ref "U2") (pin "10") (pinfunction "DIN_10") (pintype "bidirectional"))
    )
    (net (code "103") (name "Net-(U2-DOUT{slash}DRDY)") (class "Default")
      (node (ref "R13") (pin "2") (pinfunction "2_2") (pintype "passive"))
      (node (ref "U2") (pin "9") (pinfunction "DOUT/DRDY_9") (pintype "bidirectional"))
    )
    (net (code "104") (name "Net-(U2-SCLK)") (class "Default")
      (node (ref "R14") (pin "1") (pinfunction "1_1") (pintype "passive"))
      (node (ref "U2") (pin "1") (pinfunction "SCLK_1") (pintype "bidirectional"))
    )
    (net (code "105") (name "unconnected-(IC1-RA2-Pad58)") (class "Default")
      (node (ref "IC1") (pin "58") (pinfunction "RA2_58") (pintype "bidirectional"))
    )
    (net (code "106") (name "unconnected-(IC1-RA3-Pad59)") (class "Default")
      (node (ref "IC1") (pin "59") (pinfunction "RA3_59") (pintype "bidirectional"))
    )
    (net (code "107") (name "unconnected-(IC1-RA6-Pad91)") (class "Default")
      (node (ref "IC1") (pin "91") (pinfunction "RA6_91") (pintype "bidirectional"))
    )
    (net (code "108") (name "unconnected-(IC1-RA7-Pad92)") (class "Default")
      (node (ref "IC1") (pin "92") (pinfunction "RA7_92") (pintype "bidirectional"))
    )
    (net (code "109") (name "unconnected-(IC1-RA9-Pad28)") (class "Default")
      (node (ref "IC1") (pin "28") (pinfunction "RA9_28") (pintype "bidirectional"))
    )
    (net (code "110") (name "unconnected-(IC1-RA10-Pad29)") (class "Default")
      (node (ref "IC1") (pin "29") (pinfunction "RA10_29") (pintype "bidirectional"))
    )
    (net (code "111") (name "unconnected-(IC1-RA14-Pad66)") (class "Default")
      (node (ref "IC1") (pin "66") (pinfunction "RA14_66") (pintype "bidirectional"))
    )
    (net (code "112") (name "unconnected-(IC1-RA15-Pad67)") (class "Default")
      (node (ref "IC1") (pin "67") (pinfunction "RA15_67") (pintype "bidirectional"))
    )
    (net (code "113") (name "unconnected-(IC1-RB14-Pad43)") (class "Default")
      (node (ref "IC1") (pin "43") (pinfunction "RB14_43") (pintype "bidirectional"))
    )
    (net (code "114") (name "unconnected-(IC1-RB15-Pad44)") (class "Default")
      (node (ref "IC1") (pin "44") (pinfunction "RB15_44") (pintype "bidirectional"))
    )
    (net (code "115") (name "unconnected-(IC1-RC13-Pad73)") (class "Default")
      (node (ref "IC1") (pin "73") (pinfunction "RC13_73") (pintype "bidirectional"))
    )
    (net (code "116") (name "unconnected-(IC1-RC14-Pad74)") (class "Default")
      (node (ref "IC1") (pin "74") (pinfunction "RC14_74") (pintype "bidirectional"))
    )
    (net (code "117") (name "unconnected-(IC1-RD10-Pad70)") (class "Default")
      (node (ref "IC1") (pin "70") (pinfunction "RD10_70") (pintype "bidirectional"))
    )
    (net (code "118") (name "unconnected-(IC1-RD11-Pad71)") (class "Default")
      (node (ref "IC1") (pin "71") (pinfunction "RD11_71") (pintype "bidirectional"))
    )
    (net (code "119") (name "unconnected-(IC1-RD12-Pad79)") (class "Default")
      (node (ref "IC1") (pin "79") (pinfunction "RD12_79") (pintype "bidirectional"))
    )
    (net (code "120") (name "unconnected-(IC1-RD13-Pad80)") (class "Default")
      (node (ref "IC1") (pin "80") (pinfunction "RD13_80") (pintype "bidirectional"))
    )
    (net (code "121") (name "unconnected-(IC1-RD15-Pad48)") (class "Default")
      (node (ref "IC1") (pin "48") (pinfunction "RD15_48") (pintype "bidirectional"))
    )
    (net (code "122") (name "unconnected-(IC1-RF0-Pad87)") (class "Default")
      (node (ref "IC1") (pin "87") (pinfunction "RF0_87") (pintype "bidirectional"))
    )
    (net (code "123") (name "unconnected-(IC1-RF1-Pad88)") (class "Default")
      (node (ref "IC1") (pin "88") (pinfunction "RF1_88") (pintype "bidirectional"))
    )
    (net (code "124") (name "unconnected-(IC1-RF12-Pad40)") (class "Default")
      (node (ref "IC1") (pin "40") (pinfunction "RF12_40") (pintype "bidirectional"))
    )
    (net (code "125") (name "unconnected-(IC1-RF13-Pad39)") (class "Default")
      (node (ref "IC1") (pin "39") (pinfunction "RF13_39") (pintype "bidirectional"))
    )
    (net (code "126") (name "unconnected-(IC1-RG0-Pad90)") (class "Default")
      (node (ref "IC1") (pin "90") (pinfunction "RG0_90") (pintype "bidirectional"))
    )
    (net (code "127") (name "unconnected-(IC1-RG1-Pad89)") (class "Default")
      (node (ref "IC1") (pin "89") (pinfunction "RG1_89") (pintype "bidirectional"))
    )
    (net (code "128") (name "unconnected-(IC1-RG12-Pad96)") (class "Default")
      (node (ref "IC1") (pin "96") (pinfunction "RG12_96") (pintype "bidirectional"))
    )
    (net (code "129") (name "unconnected-(IC1-RG13-Pad97)") (class "Default")
      (node (ref "IC1") (pin "97") (pinfunction "RG13_97") (pintype "bidirectional"))
    )
    (net (code "130") (name "unconnected-(IC1-RG14-Pad95)") (class "Default")
      (node (ref "IC1") (pin "95") (pinfunction "RG14_95") (pintype "bidirectional"))
    )
    (net (code "131") (name "unconnected-(IC1-TCK-Pad38)") (class "Default")
      (node (ref "IC1") (pin "38") (pinfunction "TCK_38") (pintype "input"))
    )
    (net (code "132") (name "unconnected-(IC1-TDI-Pad60)") (class "Default")
      (node (ref "IC1") (pin "60") (pinfunction "TDI_60") (pintype "input"))
    )
    (net (code "133") (name "unconnected-(IC1-TDO-Pad61)") (class "Default")
      (node (ref "IC1") (pin "61") (pinfunction "TDO_61") (pintype "output"))
    )
    (net (code "134") (name "unconnected-(J2-PadA1)") (class "Default")
      (node (ref "J2") (pin "A1") (pinfunction "A1_A1") (pintype "passive"))
    )
    (net (code "135") (name "unconnected-(J2-PadA2)") (class "Default")
      (node (ref "J2") (pin "A2") (pinfunction "A2_A2") (pintype "passive"))
    )
    (net (code "136") (name "unconnected-(J2-PadA10)") (class "Default")
      (node (ref "J2") (pin "A10") (pinfunction "A10_A10") (pintype "passive"))
    )
    (net (code "137") (name "unconnected-(J2-PadA15)") (class "Default")
      (node (ref "J2") (pin "A15") (pinfunction "A15_A15") (pintype "passive"))
    )
    (net (code "138") (name "unconnected-(J2-PadA16)") (class "Default")
      (node (ref "J2") (pin "A16") (pinfunction "A16_A16") (pintype "passive"))
    )
    (net (code "139") (name "unconnected-(J2-PadA17)") (class "Default")
      (node (ref "J2") (pin "A17") (pinfunction "A17_A17") (pintype "passive"))
    )
    (net (code "140") (name "unconnected-(J2-PadA18)") (class "Default")
      (node (ref "J2") (pin "A18") (pinfunction "A18_A18") (pintype "passive"))
    )
    (net (code "141") (name "unconnected-(J2-PadA19)") (class "Default")
      (node (ref "J2") (pin "A19") (pinfunction "A19_A19") (pintype "passive"))
    )
    (net (code "142") (name "unconnected-(J2-PadA20)") (class "Default")
      (node (ref "J2") (pin "A20") (pinfunction "A20_A20") (pintype "passive"))
    )
    (net (code "143") (name "unconnected-(J2-PadA21)") (class "Default")
      (node (ref "J2") (pin "A21") (pinfunction "A21_A21") (pintype "passive"))
    )
    (net (code "144") (name "unconnected-(J2-PadA22)") (class "Default")
      (node (ref "J2") (pin "A22") (pinfunction "A22_A22") (pintype "passive"))
    )
    (net (code "145") (name "unconnected-(J2-PadA23)") (class "Default")
      (node (ref "J2") (pin "A23") (pinfunction "A23_A23") (pintype "passive"))
    )
    (net (code "146") (name "unconnected-(J2-PadA24)") (class "Default")
      (node (ref "J2") (pin "A24") (pinfunction "A24_A24") (pintype "passive"))
    )
    (net (code "147") (name "unconnected-(J2-PadA25)") (class "Default")
      (node (ref "J2") (pin "A25") (pinfunction "A25_A25") (pintype "passive"))
    )
    (net (code "148") (name "unconnected-(J2-PadA26)") (class "Default")
      (node (ref "J2") (pin "A26") (pinfunction "A26_A26") (pintype "passive"))
    )
    (net (code "149") (name "unconnected-(J2-PadA27)") (class "Default")
      (node (ref "J2") (pin "A27") (pinfunction "A27_A27") (pintype "passive"))
    )
    (net (code "150") (name "unconnected-(J2-PadA28)") (class "Default")
      (node (ref "J2") (pin "A28") (pinfunction "A28_A28") (pintype "passive"))
    )
    (net (code "151") (name "unconnected-(J2-PadA29)") (class "Default")
      (node (ref "J2") (pin "A29") (pinfunction "A29_A29") (pintype "passive"))
    )
    (net (code "152") (name "unconnected-(J2-PadA30)") (class "Default")
      (node (ref "J2") (pin "A30") (pinfunction "A30_A30") (pintype "passive"))
    )
    (net (code "153") (name "unconnected-(J2-PadA31)") (class "Default")
      (node (ref "J2") (pin "A31") (pinfunction "A31_A31") (pintype "passive"))
    )
    (net (code "154") (name "unconnected-(J2-PadA32)") (class "Default")
      (node (ref "J2") (pin "A32") (pinfunction "A32_A32") (pintype "passive"))
    )
    (net (code "155") (name "unconnected-(J2-PadB10)") (class "Default")
      (node (ref "J2") (pin "B10") (pinfunction "B10_B10") (pintype "passive"))
    )
    (net (code "156") (name "unconnected-(J2-PadB15)") (class "Default")
      (node (ref "J2") (pin "B15") (pinfunction "B15_B15") (pintype "passive"))
    )
    (net (code "157") (name "unconnected-(J2-PadB16)") (class "Default")
      (node (ref "J2") (pin "B16") (pinfunction "B16_B16") (pintype "passive"))
    )
    (net (code "158") (name "unconnected-(J2-PadB17)") (class "Default")
      (node (ref "J2") (pin "B17") (pinfunction "B17_B17") (pintype "passive"))
    )
    (net (code "159") (name "unconnected-(J2-PadB18)") (class "Default")
      (node (ref "J2") (pin "B18") (pinfunction "B18_B18") (pintype "passive"))
    )
    (net (code "160") (name "unconnected-(J2-PadB19)") (class "Default")
      (node (ref "J2") (pin "B19") (pinfunction "B19_B19") (pintype "passive"))
    )
    (net (code "161") (name "unconnected-(J2-PadB20)") (class "Default")
      (node (ref "J2") (pin "B20") (pinfunction "B20_B20") (pintype "passive"))
    )
    (net (code "162") (name "unconnected-(J2-PadB21)") (class "Default")
      (node (ref "J2") (pin "B21") (pinfunction "B21_B21") (pintype "passive"))
    )
    (net (code "163") (name "unconnected-(J2-PadB22)") (class "Default")
      (node (ref "J2") (pin "B22") (pinfunction "B22_B22") (pintype "passive"))
    )
    (net (code "164") (name "unconnected-(J2-PadB23)") (class "Default")
      (node (ref "J2") (pin "B23") (pinfunction "B23_B23") (pintype "passive"))
    )
    (net (code "165") (name "unconnected-(J2-PadB24)") (class "Default")
      (node (ref "J2") (pin "B24") (pinfunction "B24_B24") (pintype "passive"))
    )
    (net (code "166") (name "unconnected-(J2-PadB25)") (class "Default")
      (node (ref "J2") (pin "B25") (pinfunction "B25_B25") (pintype "passive"))
    )
    (net (code "167") (name "unconnected-(J2-PadB26)") (class "Default")
      (node (ref "J2") (pin "B26") (pinfunction "B26_B26") (pintype "passive"))
    )
    (net (code "168") (name "unconnected-(J2-PadB27)") (class "Default")
      (node (ref "J2") (pin "B27") (pinfunction "B27_B27") (pintype "passive"))
    )
    (net (code "169") (name "unconnected-(J2-PadB28)") (class "Default")
      (node (ref "J2") (pin "B28") (pinfunction "B28_B28") (pintype "passive"))
    )
    (net (code "170") (name "unconnected-(J2-PadB29)") (class "Default")
      (node (ref "J2") (pin "B29") (pinfunction "B29_B29") (pintype "passive"))
    )
    (net (code "171") (name "unconnected-(J2-PadB30)") (class "Default")
      (node (ref "J2") (pin "B30") (pinfunction "B30_B30") (pintype "passive"))
    )
    (net (code "172") (name "unconnected-(J2-PadB31)") (class "Default")
      (node (ref "J2") (pin "B31") (pinfunction "B31_B31") (pintype "passive"))
    )
    (net (code "173") (name "unconnected-(J2-PadB32)") (class "Default")
      (node (ref "J2") (pin "B32") (pinfunction "B32_B32") (pintype "passive"))
    )
    (net (code "174") (name "unconnected-(J2-PadC10)") (class "Default")
      (node (ref "J2") (pin "C10") (pinfunction "C10_C10") (pintype "passive"))
    )
    (net (code "175") (name "unconnected-(J2-PadC15)") (class "Default")
      (node (ref "J2") (pin "C15") (pinfunction "C15_C15") (pintype "passive"))
    )
    (net (code "176") (name "unconnected-(J2-PadC16)") (class "Default")
      (node (ref "J2") (pin "C16") (pinfunction "C16_C16") (pintype "passive"))
    )
    (net (code "177") (name "unconnected-(J2-PadC17)") (class "Default")
      (node (ref "J2") (pin "C17") (pinfunction "C17_C17") (pintype "passive"))
    )
    (net (code "178") (name "unconnected-(J2-PadC18)") (class "Default")
      (node (ref "J2") (pin "C18") (pinfunction "C18_C18") (pintype "passive"))
    )
    (net (code "179") (name "unconnected-(J2-PadC19)") (class "Default")
      (node (ref "J2") (pin "C19") (pinfunction "C19_C19") (pintype "passive"))
    )
    (net (code "180") (name "unconnected-(J2-PadC20)") (class "Default")
      (node (ref "J2") (pin "C20") (pinfunction "C20_C20") (pintype "passive"))
    )
    (net (code "181") (name "unconnected-(J2-PadC21)") (class "Default")
      (node (ref "J2") (pin "C21") (pinfunction "C21_C21") (pintype "passive"))
    )
    (net (code "182") (name "unconnected-(J2-PadC22)") (class "Default")
      (node (ref "J2") (pin "C22") (pinfunction "C22_C22") (pintype "passive"))
    )
    (net (code "183") (name "unconnected-(J2-PadC23)") (class "Default")
      (node (ref "J2") (pin "C23") (pinfunction "C23_C23") (pintype "passive"))
    )
    (net (code "184") (name "unconnected-(J2-PadC24)") (class "Default")
      (node (ref "J2") (pin "C24") (pinfunction "C24_C24") (pintype "passive"))
    )
    (net (code "185") (name "unconnected-(J2-PadC25)") (class "Default")
      (node (ref "J2") (pin "C25") (pinfunction "C25_C25") (pintype "passive"))
    )
    (net (code "186") (name "unconnected-(J2-PadC26)") (class "Default")
      (node (ref "J2") (pin "C26") (pinfunction "C26_C26") (pintype "passive"))
    )
    (net (code "187") (name "unconnected-(J2-PadC27)") (class "Default")
      (node (ref "J2") (pin "C27") (pinfunction "C27_C27") (pintype "passive"))
    )
    (net (code "188") (name "unconnected-(J2-PadC28)") (class "Default")
      (node (ref "J2") (pin "C28") (pinfunction "C28_C28") (pintype "passive"))
    )
    (net (code "189") (name "unconnected-(J2-PadC29)") (class "Default")
      (node (ref "J2") (pin "C29") (pinfunction "C29_C29") (pintype "passive"))
    )
    (net (code "190") (name "unconnected-(J2-PadC30)") (class "Default")
      (node (ref "J2") (pin "C30") (pinfunction "C30_C30") (pintype "passive"))
    )
    (net (code "191") (name "unconnected-(J2-PadC31)") (class "Default")
      (node (ref "J2") (pin "C31") (pinfunction "C31_C31") (pintype "passive"))
    )
    (net (code "192") (name "unconnected-(J2-PadC32)") (class "Default")
      (node (ref "J2") (pin "C32") (pinfunction "C32_C32") (pintype "passive"))
    )
    (net (code "193") (name "unconnected-(JP1-Pad6)") (class "Default")
      (node (ref "JP1") (pin "6") (pinfunction "6_6") (pintype "passive"))
    )
    (net (code "194") (name "unconnected-(JP2-Pad6)") (class "Default")
      (node (ref "JP2") (pin "6") (pinfunction "6_6") (pintype "passive"))
    )
    (net (code "195") (name "unconnected-(PIC16-Pad2)") (class "Default")
      (node (ref "PIC16") (pin "2") (pinfunction "2_2") (pintype "passive"))
    )
    (net (code "196") (name "unconnected-(PIC16-Pad3)") (class "Default")
      (node (ref "PIC16") (pin "3") (pinfunction "3_3") (pintype "passive"))
    )
    (net (code "197") (name "unconnected-(PIC16-Pad13)") (class "Default")
      (node (ref "PIC16") (pin "13") (pinfunction "13_13") (pintype "passive"))
    )
    (net (code "198") (name "unconnected-(U$1-CLK-Pad6)") (class "Default")
      (node (ref "U$1") (pin "6") (pinfunction "CLK_6") (pintype "bidirectional"))
    )
    (net (code "199") (name "unconnected-(U$1-CS-Pad5)") (class "Default")
      (node (ref "U$1") (pin "5") (pinfunction "CS_5") (pintype "bidirectional"))
    )
    (net (code "200") (name "unconnected-(U$1-GND2-Pad15)") (class "Default")
      (node (ref "U$1") (pin "15") (pinfunction "GND2_15") (pintype "bidirectional"))
    )
    (net (code "201") (name "unconnected-(U$1-MISO-Pad7)") (class "Default")
      (node (ref "U$1") (pin "7") (pinfunction "MISO_7") (pintype "bidirectional"))
    )
    (net (code "202") (name "unconnected-(U$1-MOSI-Pad8)") (class "Default")
      (node (ref "U$1") (pin "8") (pinfunction "MOSI_8") (pintype "bidirectional"))
    )
    (net (code "203") (name "unconnected-(U$1-NAV-Pad14)") (class "Default")
      (node (ref "U$1") (pin "14") (pinfunction "NAV_14") (pintype "bidirectional"))
    )
    (net (code "204") (name "unconnected-(U$1-RX1-Pad12)") (class "Default")
      (node (ref "U$1") (pin "12") (pinfunction "RX1_12") (pintype "bidirectional"))
    )
    (net (code "205") (name "unconnected-(U$1-SCL-Pad10)") (class "Default")
      (node (ref "U$1") (pin "10") (pinfunction "SCL_10") (pintype "bidirectional"))
    )
    (net (code "206") (name "unconnected-(U$1-SDA-Pad9)") (class "Default")
      (node (ref "U$1") (pin "9") (pinfunction "SDA_9") (pintype "bidirectional"))
    )
    (net (code "207") (name "unconnected-(U$1-TX1-Pad11)") (class "Default")
      (node (ref "U$1") (pin "11") (pinfunction "TX1_11") (pintype "bidirectional"))
    )
    (net (code "208") (name "unconnected-(X1-Pad15)") (class "Default")
      (node (ref "X1") (pin "15") (pinfunction "15_15") (pintype "passive"))
    )
    (net (code "209") (name "unconnected-(X2-Pad3)") (class "Default")
      (node (ref "X2") (pin "3") (pinfunction "3_3") (pintype "passive"))
    )
    (net (code "210") (name "unconnected-(X2-Pad7)") (class "Default")
      (node (ref "X2") (pin "7") (pinfunction "7_7") (pintype "passive"))
    )
    (net (code "211") (name "unconnected-(X2-Pad10)") (class "Default")
      (node (ref "X2") (pin "10") (pinfunction "10_10") (pintype "passive"))
    )
    (net (code "212") (name "unconnected-(X2-Pad11)") (class "Default")
      (node (ref "X2") (pin "11") (pinfunction "11_11") (pintype "passive"))
    )
  )
)
